# 03.net
KiCad netlist of a schematic drawn in EAGLE
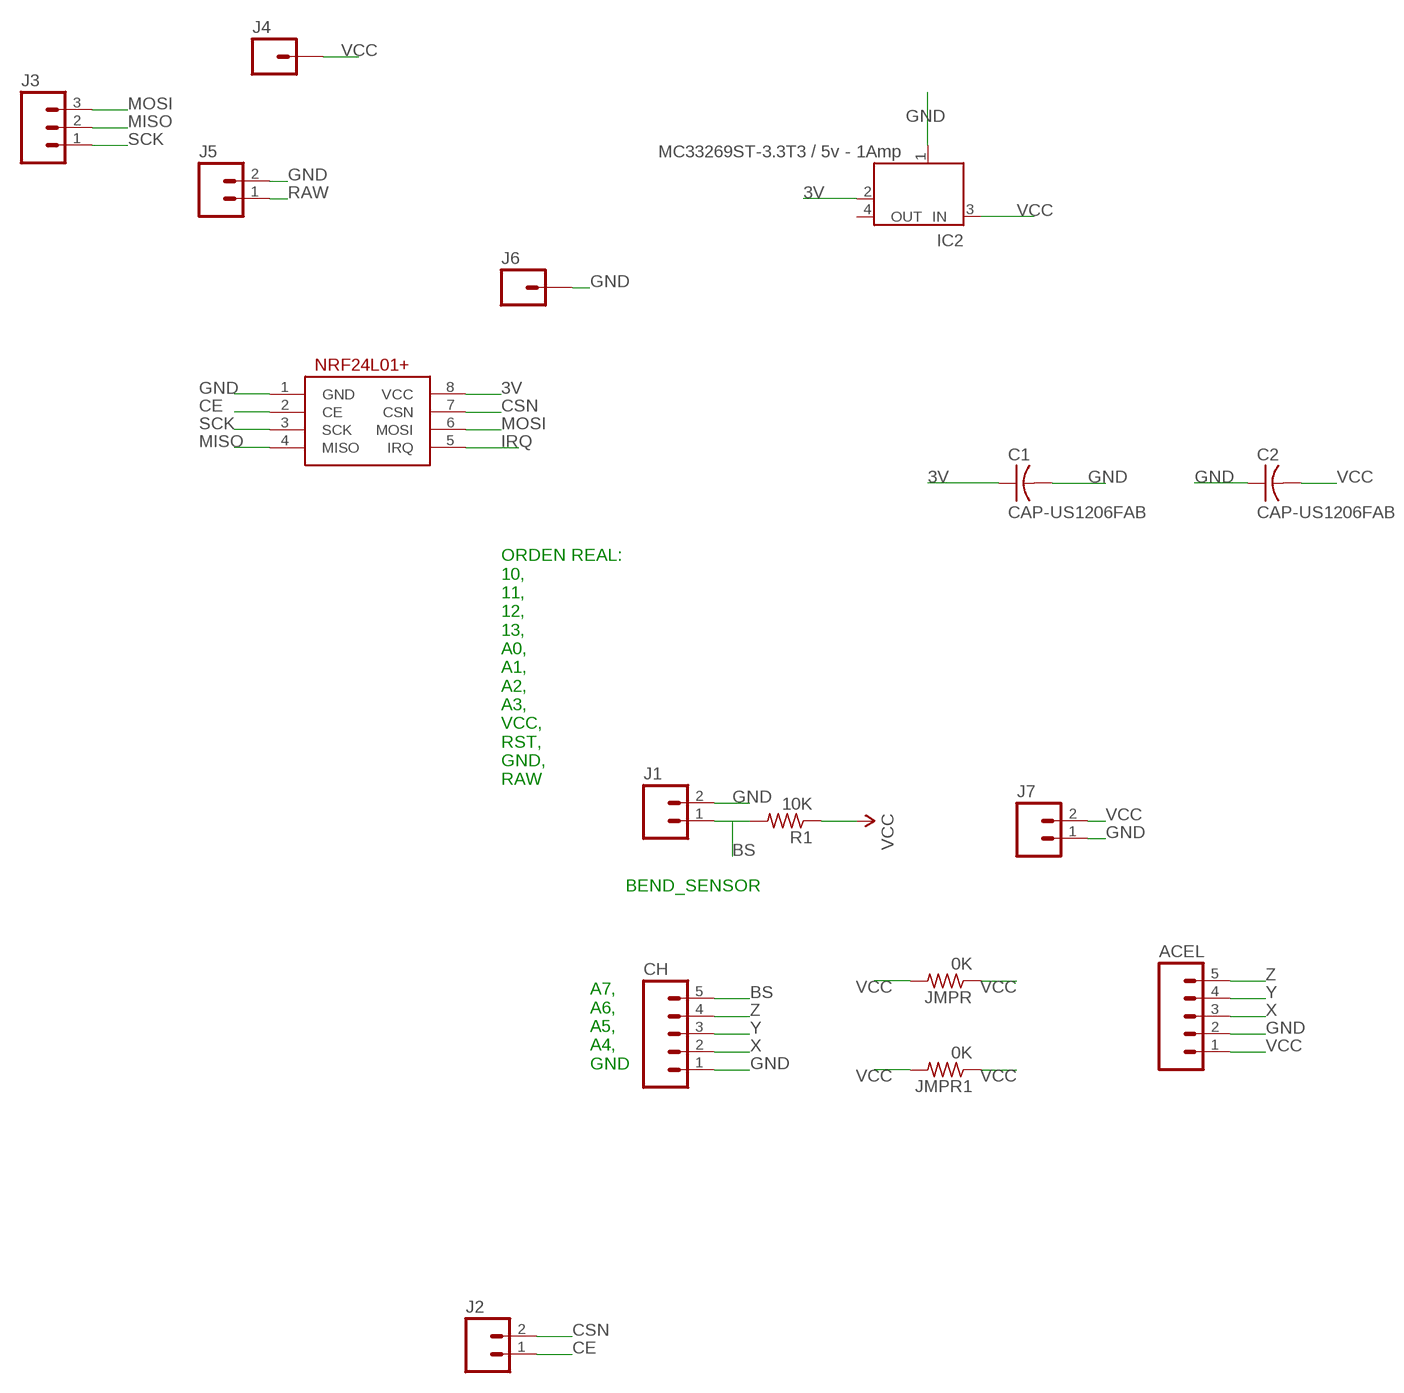
[diagram p0: schematic, sheet 1]

(export (version "E")
  (design (tool "Eeschema 10.0.6"))
  (components
    (comp (ref "ACEL")
      (value "M05NO_SILK")
      (footprint "eagle-import:1X05_NO_SILK")
      (libsource (lib "eagle-import") (part "M05NO_SILK"))
    )
    (comp (ref "C1")
      (value "CAP-US1206FAB")
      (footprint "eagle-import:C1206FAB")
      (libsource (lib "eagle-import") (part "CAP-US1206FAB"))
    )
    (comp (ref "C2")
      (value "CAP-US1206FAB")
      (footprint "eagle-import:C1206FAB")
      (libsource (lib "eagle-import") (part "CAP-US1206FAB"))
    )
    (comp (ref "CH")
      (value "M05NO_SILK")
      (footprint "eagle-import:1X05_NO_SILK")
      (libsource (lib "eagle-import") (part "M05NO_SILK"))
    )
    (comp (ref "IC2")
      (value "MC33269ST-3.3T3 / 5v - 1Amp")
      (footprint "eagle-import:SOT223")
      (libsource (lib "eagle-import") (part "MC33269ST-3.3T3"))
    )
    (comp (ref "J1")
      (value "M021X02_NO_SILK")
      (footprint "eagle-import:1X02_NO_SILK")
      (libsource (lib "eagle-import") (part "M021X02_NO_SILK"))
    )
    (comp (ref "J2")
      (value "M021X02_NO_SILK")
      (footprint "eagle-import:1X02_NO_SILK")
      (libsource (lib "eagle-import") (part "M021X02_NO_SILK"))
    )
    (comp (ref "J3")
      (value "M031X03_NO_SILK")
      (footprint "eagle-import:1X03_NO_SILK")
      (libsource (lib "eagle-import") (part "M031X03_NO_SILK"))
    )
    (comp (ref "J4")
      (value "M01NOSILK-KIT")
      (footprint "eagle-import:1X01NS-KIT")
      (libsource (lib "eagle-import") (part "M01NOSILK-KIT"))
    )
    (comp (ref "J5")
      (value "M021X02_NO_SILK")
      (footprint "eagle-import:1X02_NO_SILK")
      (libsource (lib "eagle-import") (part "M021X02_NO_SILK"))
    )
    (comp (ref "J6")
      (value "M01PTH_NO_SILK_YES_STOP")
      (footprint "eagle-import:1X01_NO_SILK")
      (libsource (lib "eagle-import") (part "M01PTH_NO_SILK_YES_STOP"))
    )
    (comp (ref "J7")
      (value "M023.5MM")
      (footprint "eagle-import:SCREWTERMINAL-3.5MM-2")
      (libsource (lib "eagle-import") (part "M023.5MM"))
    )
    (comp (ref "JMPR")
      (value "0K")
      (footprint "eagle-import:R1206FAB")
      (libsource (lib "eagle-import") (part "RES-US1206FAB"))
    )
    (comp (ref "JMPR1")
      (value "0K")
      (footprint "eagle-import:R1206FAB")
      (libsource (lib "eagle-import") (part "RES-US1206FAB"))
    )
    (comp (ref "NRF24L01+")
      (value "NRF24L01+")
      (footprint "eagle-import:2X04_THRU")
      (libsource (lib "eagle-import") (part "NRF24L01+"))
    )
    (comp (ref "R1")
      (value "10K")
      (footprint "eagle-import:R1206FAB")
      (libsource (lib "eagle-import") (part "RES-US1206FAB"))
    )
  )
  (nets
    (net (code "1") (name "/3V") (class "Default")
      (node (ref "C1") (pin "1") (pinfunction "1_1") (pintype "passive"))
      (node (ref "IC2") (pin "2") (pinfunction "OUT_2") (pintype "passive"))
      (node (ref "NRF24L01+") (pin "8") (pinfunction "VCC_8") (pintype "bidirectional"))
    )
    (net (code "2") (name "/BS") (class "Default")
      (node (ref "CH") (pin "5") (pinfunction "5_5") (pintype "passive"))
      (node (ref "J1") (pin "1") (pinfunction "1_1") (pintype "passive"))
      (node (ref "R1") (pin "2") (pinfunction "2_2") (pintype "passive"))
    )
    (net (code "3") (name "/CE") (class "Default")
      (node (ref "J2") (pin "1") (pinfunction "1_1") (pintype "passive"))
      (node (ref "NRF24L01+") (pin "2") (pinfunction "CE_2") (pintype "bidirectional"))
    )
    (net (code "4") (name "/CSN") (class "Default")
      (node (ref "J2") (pin "2") (pinfunction "2_2") (pintype "passive"))
      (node (ref "NRF24L01+") (pin "7") (pinfunction "CSN_7") (pintype "bidirectional"))
    )
    (net (code "5") (name "/GND") (class "Default")
      (node (ref "ACEL") (pin "2") (pinfunction "2_2") (pintype "passive"))
      (node (ref "C1") (pin "2") (pinfunction "2_2") (pintype "passive"))
      (node (ref "C2") (pin "1") (pinfunction "1_1") (pintype "passive"))
      (node (ref "CH") (pin "1") (pinfunction "1_1") (pintype "passive"))
      (node (ref "IC2") (pin "1") (pinfunction "GND/ADJ_1") (pintype "input"))
      (node (ref "J1") (pin "2") (pinfunction "2_2") (pintype "passive"))
      (node (ref "J5") (pin "2") (pinfunction "2_2") (pintype "passive"))
      (node (ref "J6") (pin "1") (pinfunction "1_1") (pintype "passive"))
      (node (ref "J7") (pin "1") (pinfunction "1_1") (pintype "passive"))
      (node (ref "NRF24L01+") (pin "1") (pinfunction "GND_1") (pintype "bidirectional"))
    )
    (net (code "6") (name "/IRQ") (class "Default")
      (node (ref "NRF24L01+") (pin "5") (pinfunction "IRQ_5") (pintype "bidirectional"))
    )
    (net (code "7") (name "/MISO") (class "Default")
      (node (ref "J3") (pin "2") (pinfunction "2_2") (pintype "passive"))
      (node (ref "NRF24L01+") (pin "4") (pinfunction "MISO_4") (pintype "bidirectional"))
    )
    (net (code "8") (name "/MOSI") (class "Default")
      (node (ref "J3") (pin "3") (pinfunction "3_3") (pintype "passive"))
      (node (ref "NRF24L01+") (pin "6") (pinfunction "MOSI_6") (pintype "bidirectional"))
    )
    (net (code "9") (name "/RAW") (class "Default")
      (node (ref "J5") (pin "1") (pinfunction "1_1") (pintype "passive"))
    )
    (net (code "10") (name "/SCK") (class "Default")
      (node (ref "J3") (pin "1") (pinfunction "1_1") (pintype "passive"))
      (node (ref "NRF24L01+") (pin "3") (pinfunction "SCK_3") (pintype "bidirectional"))
    )
    (net (code "11") (name "/X") (class "Default")
      (node (ref "ACEL") (pin "3") (pinfunction "3_3") (pintype "passive"))
      (node (ref "CH") (pin "2") (pinfunction "2_2") (pintype "passive"))
    )
    (net (code "12") (name "/Y") (class "Default")
      (node (ref "ACEL") (pin "4") (pinfunction "4_4") (pintype "passive"))
      (node (ref "CH") (pin "3") (pinfunction "3_3") (pintype "passive"))
    )
    (net (code "13") (name "/Z") (class "Default")
      (node (ref "ACEL") (pin "5") (pinfunction "5_5") (pintype "passive"))
      (node (ref "CH") (pin "4") (pinfunction "4_4") (pintype "passive"))
    )
    (net (code "14") (name "VCC") (class "Default")
      (node (ref "ACEL") (pin "1") (pinfunction "1_1") (pintype "passive"))
      (node (ref "C2") (pin "2") (pinfunction "2_2") (pintype "passive"))
      (node (ref "IC2") (pin "3") (pinfunction "IN_3") (pintype "input"))
      (node (ref "J4") (pin "1") (pinfunction "1_1") (pintype "passive"))
      (node (ref "J7") (pin "2") (pinfunction "2_2") (pintype "passive"))
      (node (ref "JMPR") (pin "1") (pinfunction "1_1") (pintype "passive"))
      (node (ref "JMPR") (pin "2") (pinfunction "2_2") (pintype "passive"))
      (node (ref "JMPR1") (pin "1") (pinfunction "1_1") (pintype "passive"))
      (node (ref "JMPR1") (pin "2") (pinfunction "2_2") (pintype "passive"))
      (node (ref "R1") (pin "1") (pinfunction "1_1") (pintype "passive"))
    )
    (net (code "15") (name "unconnected-(IC2-OUT-Pad4)") (class "Default")
      (node (ref "IC2") (pin "4") (pinfunction "OUT_4") (pintype "passive"))
    )
  )
)
